# I2C_T.net
KiCad netlist of a schematic drawn in EAGLE
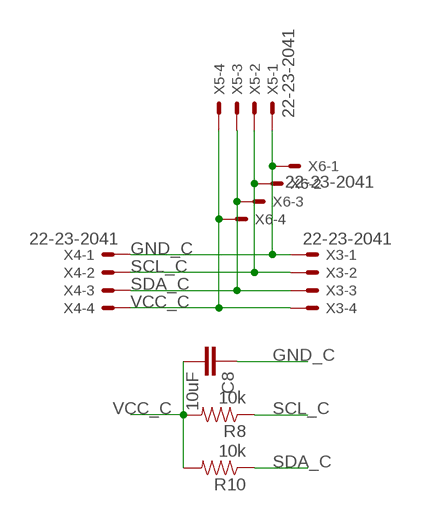
[diagram p0: schematic, sheet 1]

(export (version "E")
  (design (tool "Eeschema 10.0.6"))
  (components
    (comp (ref "C8")
      (value "10uF")
      (footprint "eagle-import:0805-CAP")
      (libsource (lib "eagle-import") (part "10UF10V10%(0805)"))
    )
    (comp (ref "R8")
      (value "10k")
      (footprint "eagle-import:0805")
      (libsource (lib "eagle-import") (part "0.3OHM-1/8W-1%(0805)"))
    )
    (comp (ref "R10")
      (value "10k")
      (footprint "eagle-import:0805")
      (libsource (lib "eagle-import") (part "0.3OHM-1/8W-1%(0805)"))
    )
    (comp (ref "X3")
      (value "22-23-2041")
      (footprint "eagle-import:22-23-2041")
      (fields (field (name "MF") "MOLEX"))
      (libsource (lib "eagle-import") (part "22-23-2041"))
    )
    (comp (ref "X4")
      (value "22-23-2041")
      (footprint "eagle-import:22-23-2041")
      (fields (field (name "MF") "MOLEX"))
      (libsource (lib "eagle-import") (part "22-23-2041"))
    )
    (comp (ref "X5")
      (value "22-23-2041")
      (footprint "eagle-import:22-23-2041")
      (fields (field (name "MF") "MOLEX"))
      (libsource (lib "eagle-import") (part "22-23-2041"))
    )
    (comp (ref "X6")
      (value "22-23-2041")
      (footprint "eagle-import:22-23-2041")
      (fields (field (name "MF") "MOLEX"))
      (libsource (lib "eagle-import") (part "22-23-2041"))
    )
  )
  (nets
    (net (code "1") (name "/GND_C") (class "Default")
      (node (ref "C8") (pin "1") (pinfunction "1_1") (pintype "passive"))
      (node (ref "X3") (pin "1") (pinfunction "S_1") (pintype "passive"))
      (node (ref "X4") (pin "1") (pinfunction "S_1") (pintype "passive"))
      (node (ref "X5") (pin "1") (pinfunction "S_1") (pintype "passive"))
      (node (ref "X6") (pin "1") (pinfunction "S_1") (pintype "passive"))
    )
    (net (code "2") (name "/SCL_C") (class "Default")
      (node (ref "R8") (pin "1") (pinfunction "1_1") (pintype "passive"))
      (node (ref "X3") (pin "2") (pinfunction "S_2") (pintype "passive"))
      (node (ref "X4") (pin "2") (pinfunction "S_2") (pintype "passive"))
      (node (ref "X5") (pin "2") (pinfunction "S_2") (pintype "passive"))
      (node (ref "X6") (pin "2") (pinfunction "S_2") (pintype "passive"))
    )
    (net (code "3") (name "/SDA_C") (class "Default")
      (node (ref "R10") (pin "1") (pinfunction "1_1") (pintype "passive"))
      (node (ref "X3") (pin "3") (pinfunction "S_3") (pintype "passive"))
      (node (ref "X4") (pin "3") (pinfunction "S_3") (pintype "passive"))
      (node (ref "X5") (pin "3") (pinfunction "S_3") (pintype "passive"))
      (node (ref "X6") (pin "3") (pinfunction "S_3") (pintype "passive"))
    )
    (net (code "4") (name "/VCC_C") (class "Default")
      (node (ref "C8") (pin "2") (pinfunction "2_2") (pintype "passive"))
      (node (ref "R10") (pin "2") (pinfunction "2_2") (pintype "passive"))
      (node (ref "R8") (pin "2") (pinfunction "2_2") (pintype "passive"))
      (node (ref "X3") (pin "4") (pinfunction "S_4") (pintype "passive"))
      (node (ref "X4") (pin "4") (pinfunction "S_4") (pintype "passive"))
      (node (ref "X5") (pin "4") (pinfunction "S_4") (pintype "passive"))
      (node (ref "X6") (pin "4") (pinfunction "S_4") (pintype "passive"))
    )
  )
)
